# tact-switches.net
KiCad netlist of a schematic drawn in EAGLE
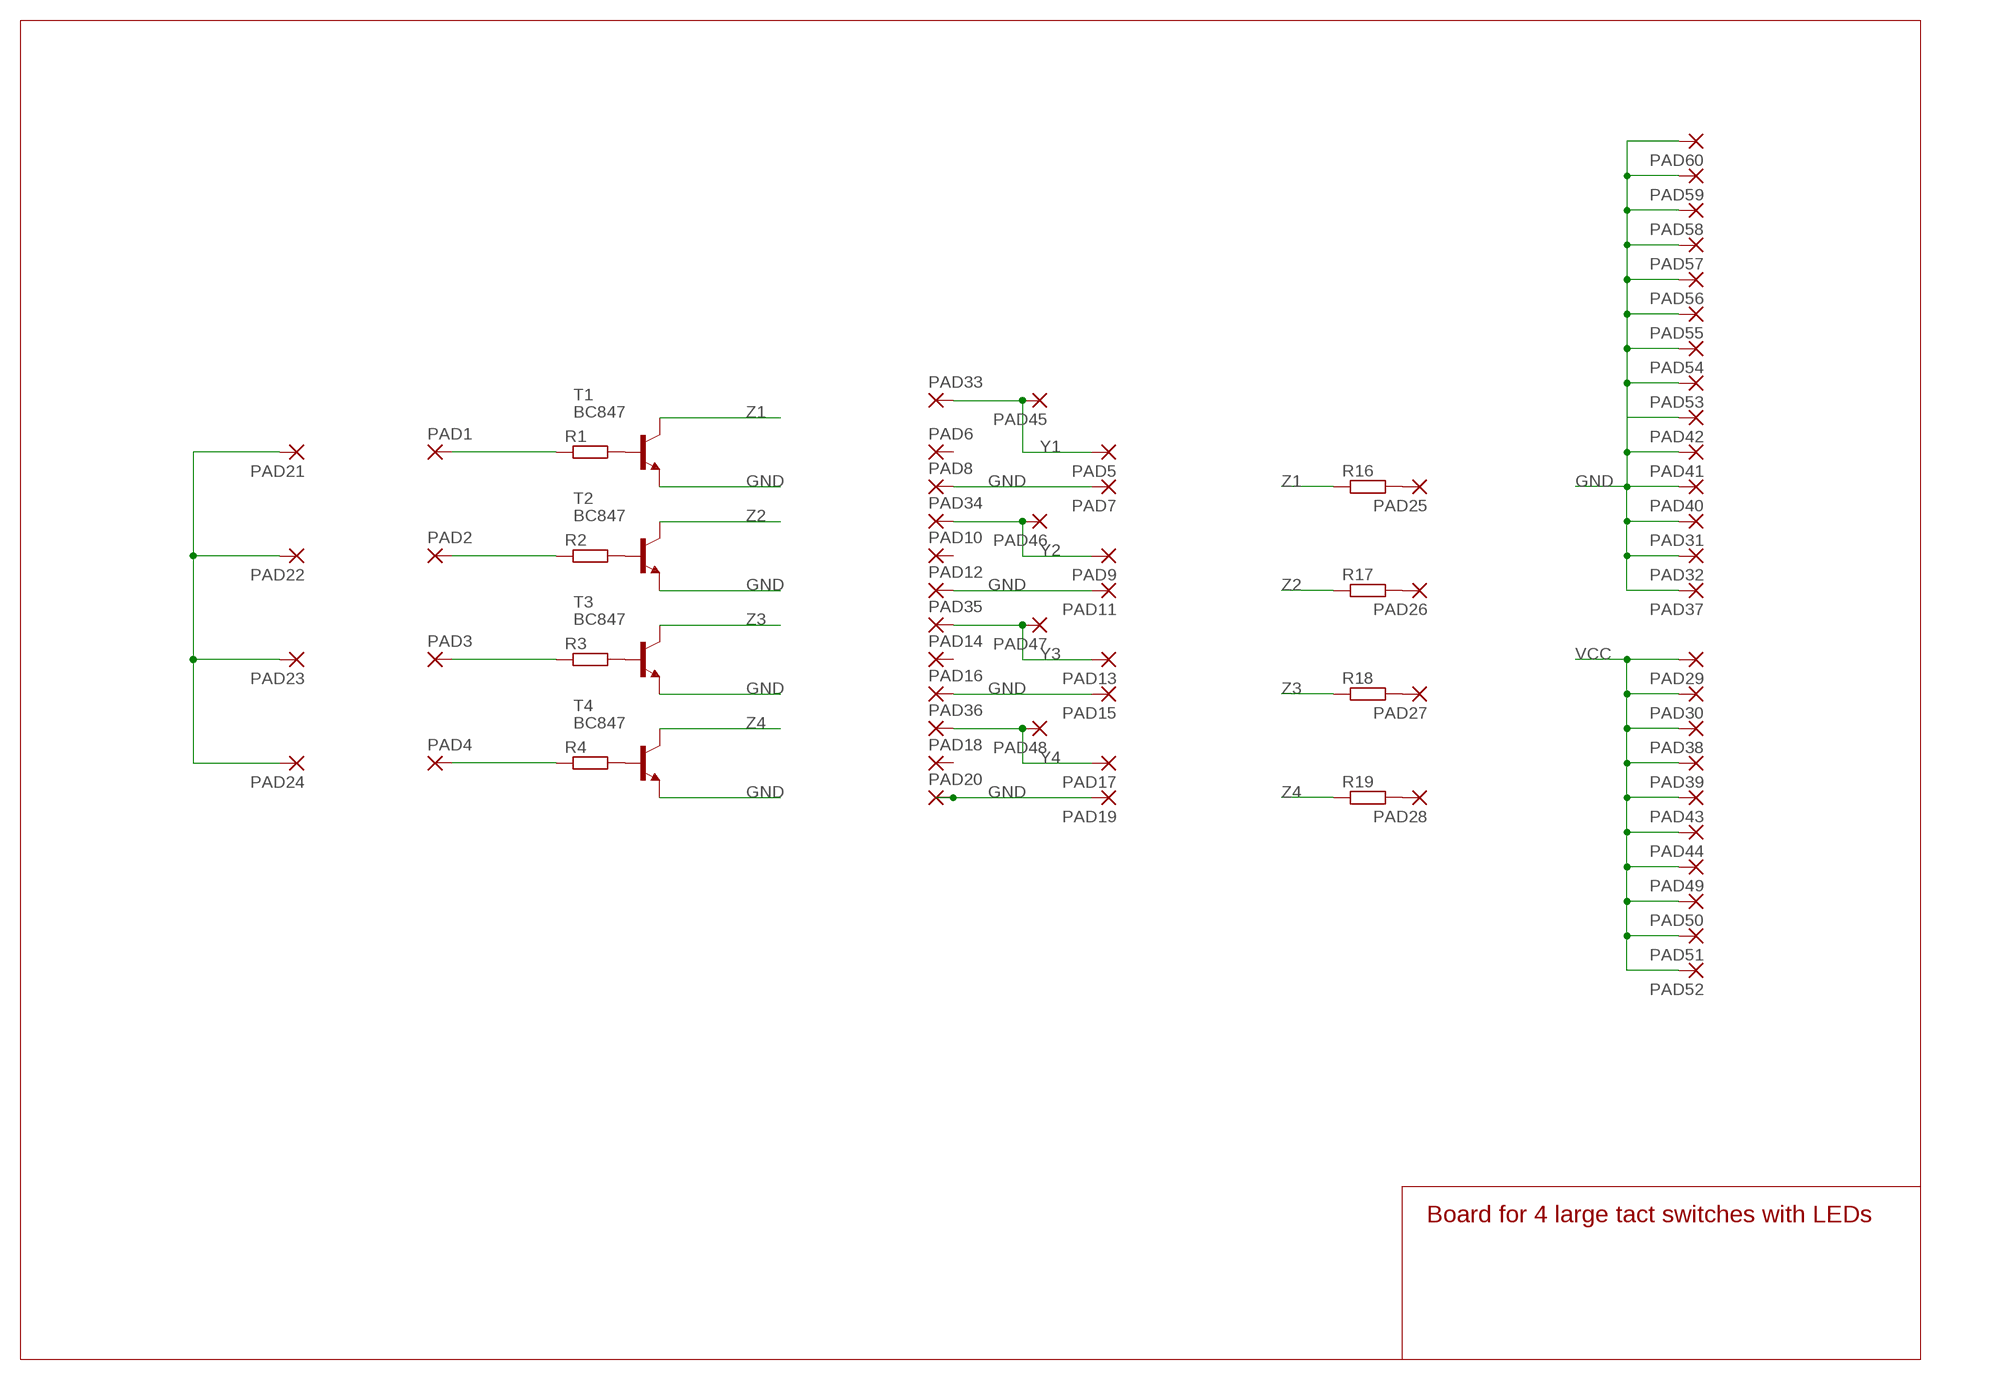
[diagram p0: schematic, sheet 1]

(export (version "E")
  (design (tool "Eeschema 10.0.6"))
  (components
    (comp (ref "PAD1")
      (value "1,6/0,8")
      (footprint "eagle-import:1,6_0,8")
      (libsource (lib "eagle-import") (part "1,6/0,8"))
    )
    (comp (ref "PAD2")
      (value "1,6/0,8")
      (footprint "eagle-import:1,6_0,8")
      (libsource (lib "eagle-import") (part "1,6/0,8"))
    )
    (comp (ref "PAD3")
      (value "1,6/0,8")
      (footprint "eagle-import:1,6_0,8")
      (libsource (lib "eagle-import") (part "1,6/0,8"))
    )
    (comp (ref "PAD4")
      (value "1,6/0,8")
      (footprint "eagle-import:1,6_0,8")
      (libsource (lib "eagle-import") (part "1,6/0,8"))
    )
    (comp (ref "PAD5")
      (value "1,6/0,8")
      (footprint "eagle-import:1,6_0,8")
      (libsource (lib "eagle-import") (part "1,6/0,8"))
    )
    (comp (ref "PAD6")
      (value "1,6/0,8")
      (footprint "eagle-import:1,6_0,8")
      (libsource (lib "eagle-import") (part "1,6/0,8"))
    )
    (comp (ref "PAD7")
      (value "1,6/0,8")
      (footprint "eagle-import:1,6_0,8")
      (libsource (lib "eagle-import") (part "1,6/0,8"))
    )
    (comp (ref "PAD8")
      (value "1,6/0,8")
      (footprint "eagle-import:1,6_0,8")
      (libsource (lib "eagle-import") (part "1,6/0,8"))
    )
    (comp (ref "PAD9")
      (value "1,6/0,8")
      (footprint "eagle-import:1,6_0,8")
      (libsource (lib "eagle-import") (part "1,6/0,8"))
    )
    (comp (ref "PAD10")
      (value "1,6/0,8")
      (footprint "eagle-import:1,6_0,8")
      (libsource (lib "eagle-import") (part "1,6/0,8"))
    )
    (comp (ref "PAD11")
      (value "1,6/0,8")
      (footprint "eagle-import:1,6_0,8")
      (libsource (lib "eagle-import") (part "1,6/0,8"))
    )
    (comp (ref "PAD12")
      (value "1,6/0,8")
      (footprint "eagle-import:1,6_0,8")
      (libsource (lib "eagle-import") (part "1,6/0,8"))
    )
    (comp (ref "PAD13")
      (value "1,6/0,8")
      (footprint "eagle-import:1,6_0,8")
      (libsource (lib "eagle-import") (part "1,6/0,8"))
    )
    (comp (ref "PAD14")
      (value "1,6/0,8")
      (footprint "eagle-import:1,6_0,8")
      (libsource (lib "eagle-import") (part "1,6/0,8"))
    )
    (comp (ref "PAD15")
      (value "1,6/0,8")
      (footprint "eagle-import:1,6_0,8")
      (libsource (lib "eagle-import") (part "1,6/0,8"))
    )
    (comp (ref "PAD16")
      (value "1,6/0,8")
      (footprint "eagle-import:1,6_0,8")
      (libsource (lib "eagle-import") (part "1,6/0,8"))
    )
    (comp (ref "PAD17")
      (value "1,6/0,8")
      (footprint "eagle-import:1,6_0,8")
      (libsource (lib "eagle-import") (part "1,6/0,8"))
    )
    (comp (ref "PAD18")
      (value "1,6/0,8")
      (footprint "eagle-import:1,6_0,8")
      (libsource (lib "eagle-import") (part "1,6/0,8"))
    )
    (comp (ref "PAD19")
      (value "1,6/0,8")
      (footprint "eagle-import:1,6_0,8")
      (libsource (lib "eagle-import") (part "1,6/0,8"))
    )
    (comp (ref "PAD20")
      (value "1,6/0,8")
      (footprint "eagle-import:1,6_0,8")
      (libsource (lib "eagle-import") (part "1,6/0,8"))
    )
    (comp (ref "PAD21")
      (value "1,6/0,8")
      (footprint "eagle-import:1,6_0,8")
      (libsource (lib "eagle-import") (part "1,6/0,8"))
    )
    (comp (ref "PAD22")
      (value "1,6/0,8")
      (footprint "eagle-import:1,6_0,8")
      (libsource (lib "eagle-import") (part "1,6/0,8"))
    )
    (comp (ref "PAD23")
      (value "1,6/0,8")
      (footprint "eagle-import:1,6_0,8")
      (libsource (lib "eagle-import") (part "1,6/0,8"))
    )
    (comp (ref "PAD24")
      (value "1,6/0,8")
      (footprint "eagle-import:1,6_0,8")
      (libsource (lib "eagle-import") (part "1,6/0,8"))
    )
    (comp (ref "PAD25")
      (value "1,6/0,8")
      (footprint "eagle-import:1,6_0,8")
      (libsource (lib "eagle-import") (part "1,6/0,8"))
    )
    (comp (ref "PAD26")
      (value "1,6/0,8")
      (footprint "eagle-import:1,6_0,8")
      (libsource (lib "eagle-import") (part "1,6/0,8"))
    )
    (comp (ref "PAD27")
      (value "1,6/0,8")
      (footprint "eagle-import:1,6_0,8")
      (libsource (lib "eagle-import") (part "1,6/0,8"))
    )
    (comp (ref "PAD28")
      (value "1,6/0,8")
      (footprint "eagle-import:1,6_0,8")
      (libsource (lib "eagle-import") (part "1,6/0,8"))
    )
    (comp (ref "PAD29")
      (value "1,6/0,8")
      (footprint "eagle-import:1,6_0,8")
      (libsource (lib "eagle-import") (part "1,6/0,8"))
    )
    (comp (ref "PAD30")
      (value "1,6/0,8")
      (footprint "eagle-import:1,6_0,8")
      (libsource (lib "eagle-import") (part "1,6/0,8"))
    )
    (comp (ref "PAD31")
      (value "1,6/0,8")
      (footprint "eagle-import:1,6_0,8")
      (libsource (lib "eagle-import") (part "1,6/0,8"))
    )
    (comp (ref "PAD32")
      (value "1,6/0,8")
      (footprint "eagle-import:1,6_0,8")
      (libsource (lib "eagle-import") (part "1,6/0,8"))
    )
    (comp (ref "PAD33")
      (value "1,6/0,8")
      (footprint "eagle-import:1,6_0,8")
      (libsource (lib "eagle-import") (part "1,6/0,8"))
    )
    (comp (ref "PAD34")
      (value "1,6/0,8")
      (footprint "eagle-import:1,6_0,8")
      (libsource (lib "eagle-import") (part "1,6/0,8"))
    )
    (comp (ref "PAD35")
      (value "1,6/0,8")
      (footprint "eagle-import:1,6_0,8")
      (libsource (lib "eagle-import") (part "1,6/0,8"))
    )
    (comp (ref "PAD36")
      (value "1,6/0,8")
      (footprint "eagle-import:1,6_0,8")
      (libsource (lib "eagle-import") (part "1,6/0,8"))
    )
    (comp (ref "PAD37")
      (value "1,6/0,8")
      (footprint "eagle-import:1,6_0,8")
      (libsource (lib "eagle-import") (part "1,6/0,8"))
    )
    (comp (ref "PAD38")
      (value "1,6/0,8")
      (footprint "eagle-import:1,6_0,8")
      (libsource (lib "eagle-import") (part "1,6/0,8"))
    )
    (comp (ref "PAD39")
      (value "1,6/0,8")
      (footprint "eagle-import:1,6_0,8")
      (libsource (lib "eagle-import") (part "1,6/0,8"))
    )
    (comp (ref "PAD40")
      (value "1,6/0,8")
      (footprint "eagle-import:1,6_0,8")
      (libsource (lib "eagle-import") (part "1,6/0,8"))
    )
    (comp (ref "PAD41")
      (value "1,6/0,8")
      (footprint "eagle-import:1,6_0,8")
      (libsource (lib "eagle-import") (part "1,6/0,8"))
    )
    (comp (ref "PAD42")
      (value "1,6/0,8")
      (footprint "eagle-import:1,6_0,8")
      (libsource (lib "eagle-import") (part "1,6/0,8"))
    )
    (comp (ref "PAD43")
      (value "1,6/0,8")
      (footprint "eagle-import:1,6_0,8")
      (libsource (lib "eagle-import") (part "1,6/0,8"))
    )
    (comp (ref "PAD44")
      (value "1,6/0,8")
      (footprint "eagle-import:1,6_0,8")
      (libsource (lib "eagle-import") (part "1,6/0,8"))
    )
    (comp (ref "PAD45")
      (value "1,6/0,8")
      (footprint "eagle-import:1,6_0,8")
      (libsource (lib "eagle-import") (part "1,6/0,8"))
    )
    (comp (ref "PAD46")
      (value "1,6/0,8")
      (footprint "eagle-import:1,6_0,8")
      (libsource (lib "eagle-import") (part "1,6/0,8"))
    )
    (comp (ref "PAD47")
      (value "1,6/0,8")
      (footprint "eagle-import:1,6_0,8")
      (libsource (lib "eagle-import") (part "1,6/0,8"))
    )
    (comp (ref "PAD48")
      (value "1,6/0,8")
      (footprint "eagle-import:1,6_0,8")
      (libsource (lib "eagle-import") (part "1,6/0,8"))
    )
    (comp (ref "PAD49")
      (value "1,6/0,8")
      (footprint "eagle-import:1,6_0,8")
      (libsource (lib "eagle-import") (part "1,6/0,8"))
    )
    (comp (ref "PAD50")
      (value "1,6/0,8")
      (footprint "eagle-import:1,6_0,8")
      (libsource (lib "eagle-import") (part "1,6/0,8"))
    )
    (comp (ref "PAD51")
      (value "1,6/0,8")
      (footprint "eagle-import:1,6_0,8")
      (libsource (lib "eagle-import") (part "1,6/0,8"))
    )
    (comp (ref "PAD52")
      (value "1,6/0,8")
      (footprint "eagle-import:1,6_0,8")
      (libsource (lib "eagle-import") (part "1,6/0,8"))
    )
    (comp (ref "PAD53")
      (value "1,6/0,8")
      (footprint "eagle-import:1,6_0,8")
      (libsource (lib "eagle-import") (part "1,6/0,8"))
    )
    (comp (ref "PAD54")
      (value "1,6/0,8")
      (footprint "eagle-import:1,6_0,8")
      (libsource (lib "eagle-import") (part "1,6/0,8"))
    )
    (comp (ref "PAD55")
      (value "1,6/0,8")
      (footprint "eagle-import:1,6_0,8")
      (libsource (lib "eagle-import") (part "1,6/0,8"))
    )
    (comp (ref "PAD56")
      (value "1,6/0,8")
      (footprint "eagle-import:1,6_0,8")
      (libsource (lib "eagle-import") (part "1,6/0,8"))
    )
    (comp (ref "PAD57")
      (value "1,6/0,8")
      (footprint "eagle-import:1,6_0,8")
      (libsource (lib "eagle-import") (part "1,6/0,8"))
    )
    (comp (ref "PAD58")
      (value "1,6/0,8")
      (footprint "eagle-import:1,6_0,8")
      (libsource (lib "eagle-import") (part "1,6/0,8"))
    )
    (comp (ref "PAD59")
      (value "1,6/0,8")
      (footprint "eagle-import:1,6_0,8")
      (libsource (lib "eagle-import") (part "1,6/0,8"))
    )
    (comp (ref "PAD60")
      (value "1,6/0,8")
      (footprint "eagle-import:1,6_0,8")
      (libsource (lib "eagle-import") (part "1,6/0,8"))
    )
    (comp (ref "R1")
      (value "R-EU_M0805")
      (footprint "eagle-import:M0805")
      (libsource (lib "eagle-import") (part "R-EU_M0805"))
    )
    (comp (ref "R2")
      (value "R-EU_M0805")
      (footprint "eagle-import:M0805")
      (libsource (lib "eagle-import") (part "R-EU_M0805"))
    )
    (comp (ref "R3")
      (value "R-EU_M0805")
      (footprint "eagle-import:M0805")
      (libsource (lib "eagle-import") (part "R-EU_M0805"))
    )
    (comp (ref "R4")
      (value "R-EU_M0805")
      (footprint "eagle-import:M0805")
      (libsource (lib "eagle-import") (part "R-EU_M0805"))
    )
    (comp (ref "R16")
      (value "R-EU_M0805")
      (footprint "eagle-import:M0805")
      (libsource (lib "eagle-import") (part "R-EU_M0805"))
    )
    (comp (ref "R17")
      (value "R-EU_M0805")
      (footprint "eagle-import:M0805")
      (libsource (lib "eagle-import") (part "R-EU_M0805"))
    )
    (comp (ref "R18")
      (value "R-EU_M0805")
      (footprint "eagle-import:M0805")
      (libsource (lib "eagle-import") (part "R-EU_M0805"))
    )
    (comp (ref "R19")
      (value "R-EU_M0805")
      (footprint "eagle-import:M0805")
      (libsource (lib "eagle-import") (part "R-EU_M0805"))
    )
    (comp (ref "T1")
      (value "BC847")
      (footprint "eagle-import:SOT23")
      (libsource (lib "eagle-import") (part "BC847"))
    )
    (comp (ref "T2")
      (value "BC847")
      (footprint "eagle-import:SOT23")
      (libsource (lib "eagle-import") (part "BC847"))
    )
    (comp (ref "T3")
      (value "BC847")
      (footprint "eagle-import:SOT23")
      (libsource (lib "eagle-import") (part "BC847"))
    )
    (comp (ref "T4")
      (value "BC847")
      (footprint "eagle-import:SOT23")
      (libsource (lib "eagle-import") (part "BC847"))
    )
  )
  (nets
    (net (code "1") (name "/GND") (class "Default")
      (node (ref "PAD11") (pin "1") (pinfunction "P_1") (pintype "passive"))
      (node (ref "PAD12") (pin "1") (pinfunction "P_1") (pintype "passive"))
      (node (ref "PAD15") (pin "1") (pinfunction "P_1") (pintype "passive"))
      (node (ref "PAD16") (pin "1") (pinfunction "P_1") (pintype "passive"))
      (node (ref "PAD19") (pin "1") (pinfunction "P_1") (pintype "passive"))
      (node (ref "PAD20") (pin "1") (pinfunction "P_1") (pintype "passive"))
      (node (ref "PAD31") (pin "1") (pinfunction "P_1") (pintype "passive"))
      (node (ref "PAD32") (pin "1") (pinfunction "P_1") (pintype "passive"))
      (node (ref "PAD37") (pin "1") (pinfunction "P_1") (pintype "passive"))
      (node (ref "PAD40") (pin "1") (pinfunction "P_1") (pintype "passive"))
      (node (ref "PAD41") (pin "1") (pinfunction "P_1") (pintype "passive"))
      (node (ref "PAD42") (pin "1") (pinfunction "P_1") (pintype "passive"))
      (node (ref "PAD53") (pin "1") (pinfunction "P_1") (pintype "passive"))
      (node (ref "PAD54") (pin "1") (pinfunction "P_1") (pintype "passive"))
      (node (ref "PAD55") (pin "1") (pinfunction "P_1") (pintype "passive"))
      (node (ref "PAD56") (pin "1") (pinfunction "P_1") (pintype "passive"))
      (node (ref "PAD57") (pin "1") (pinfunction "P_1") (pintype "passive"))
      (node (ref "PAD58") (pin "1") (pinfunction "P_1") (pintype "passive"))
      (node (ref "PAD59") (pin "1") (pinfunction "P_1") (pintype "passive"))
      (node (ref "PAD60") (pin "1") (pinfunction "P_1") (pintype "passive"))
      (node (ref "PAD7") (pin "1") (pinfunction "P_1") (pintype "passive"))
      (node (ref "PAD8") (pin "1") (pinfunction "P_1") (pintype "passive"))
      (node (ref "T1") (pin "2") (pinfunction "E_2") (pintype "passive"))
      (node (ref "T2") (pin "2") (pinfunction "E_2") (pintype "passive"))
      (node (ref "T3") (pin "2") (pinfunction "E_2") (pintype "passive"))
      (node (ref "T4") (pin "2") (pinfunction "E_2") (pintype "passive"))
    )
    (net (code "2") (name "/VCC") (class "Default")
      (node (ref "PAD29") (pin "1") (pinfunction "P_1") (pintype "passive"))
      (node (ref "PAD30") (pin "1") (pinfunction "P_1") (pintype "passive"))
      (node (ref "PAD38") (pin "1") (pinfunction "P_1") (pintype "passive"))
      (node (ref "PAD39") (pin "1") (pinfunction "P_1") (pintype "passive"))
      (node (ref "PAD43") (pin "1") (pinfunction "P_1") (pintype "passive"))
      (node (ref "PAD44") (pin "1") (pinfunction "P_1") (pintype "passive"))
      (node (ref "PAD49") (pin "1") (pinfunction "P_1") (pintype "passive"))
      (node (ref "PAD50") (pin "1") (pinfunction "P_1") (pintype "passive"))
      (node (ref "PAD51") (pin "1") (pinfunction "P_1") (pintype "passive"))
      (node (ref "PAD52") (pin "1") (pinfunction "P_1") (pintype "passive"))
    )
    (net (code "3") (name "/Y1") (class "Default")
      (node (ref "PAD33") (pin "1") (pinfunction "P_1") (pintype "passive"))
      (node (ref "PAD45") (pin "1") (pinfunction "P_1") (pintype "passive"))
      (node (ref "PAD5") (pin "1") (pinfunction "P_1") (pintype "passive"))
    )
    (net (code "4") (name "/Y2") (class "Default")
      (node (ref "PAD34") (pin "1") (pinfunction "P_1") (pintype "passive"))
      (node (ref "PAD46") (pin "1") (pinfunction "P_1") (pintype "passive"))
      (node (ref "PAD9") (pin "1") (pinfunction "P_1") (pintype "passive"))
    )
    (net (code "5") (name "/Y3") (class "Default")
      (node (ref "PAD13") (pin "1") (pinfunction "P_1") (pintype "passive"))
      (node (ref "PAD35") (pin "1") (pinfunction "P_1") (pintype "passive"))
      (node (ref "PAD47") (pin "1") (pinfunction "P_1") (pintype "passive"))
    )
    (net (code "6") (name "/Y4") (class "Default")
      (node (ref "PAD17") (pin "1") (pinfunction "P_1") (pintype "passive"))
      (node (ref "PAD36") (pin "1") (pinfunction "P_1") (pintype "passive"))
      (node (ref "PAD48") (pin "1") (pinfunction "P_1") (pintype "passive"))
    )
    (net (code "7") (name "/Z1") (class "Default")
      (node (ref "R16") (pin "1") (pinfunction "1_1") (pintype "passive"))
      (node (ref "T1") (pin "3") (pinfunction "C_3") (pintype "passive"))
    )
    (net (code "8") (name "/Z2") (class "Default")
      (node (ref "R17") (pin "1") (pinfunction "1_1") (pintype "passive"))
      (node (ref "T2") (pin "3") (pinfunction "C_3") (pintype "passive"))
    )
    (net (code "9") (name "/Z3") (class "Default")
      (node (ref "R18") (pin "1") (pinfunction "1_1") (pintype "passive"))
      (node (ref "T3") (pin "3") (pinfunction "C_3") (pintype "passive"))
    )
    (net (code "10") (name "/Z4") (class "Default")
      (node (ref "R19") (pin "1") (pinfunction "1_1") (pintype "passive"))
      (node (ref "T4") (pin "3") (pinfunction "C_3") (pintype "passive"))
    )
    (net (code "11") (name "Net-(PAD1-P)") (class "Default")
      (node (ref "PAD1") (pin "1") (pinfunction "P_1") (pintype "passive"))
      (node (ref "R1") (pin "1") (pinfunction "1_1") (pintype "passive"))
    )
    (net (code "12") (name "Net-(PAD2-P)") (class "Default")
      (node (ref "PAD2") (pin "1") (pinfunction "P_1") (pintype "passive"))
      (node (ref "R2") (pin "1") (pinfunction "1_1") (pintype "passive"))
    )
    (net (code "13") (name "Net-(PAD3-P)") (class "Default")
      (node (ref "PAD3") (pin "1") (pinfunction "P_1") (pintype "passive"))
      (node (ref "R3") (pin "1") (pinfunction "1_1") (pintype "passive"))
    )
    (net (code "14") (name "Net-(PAD4-P)") (class "Default")
      (node (ref "PAD4") (pin "1") (pinfunction "P_1") (pintype "passive"))
      (node (ref "R4") (pin "1") (pinfunction "1_1") (pintype "passive"))
    )
    (net (code "15") (name "Net-(PAD21-P)") (class "Default")
      (node (ref "PAD21") (pin "1") (pinfunction "P_1") (pintype "passive"))
      (node (ref "PAD22") (pin "1") (pinfunction "P_1") (pintype "passive"))
      (node (ref "PAD23") (pin "1") (pinfunction "P_1") (pintype "passive"))
      (node (ref "PAD24") (pin "1") (pinfunction "P_1") (pintype "passive"))
    )
    (net (code "16") (name "Net-(PAD25-P)") (class "Default")
      (node (ref "PAD25") (pin "1") (pinfunction "P_1") (pintype "passive"))
      (node (ref "R16") (pin "2") (pinfunction "2_2") (pintype "passive"))
    )
    (net (code "17") (name "Net-(PAD26-P)") (class "Default")
      (node (ref "PAD26") (pin "1") (pinfunction "P_1") (pintype "passive"))
      (node (ref "R17") (pin "2") (pinfunction "2_2") (pintype "passive"))
    )
    (net (code "18") (name "Net-(PAD27-P)") (class "Default")
      (node (ref "PAD27") (pin "1") (pinfunction "P_1") (pintype "passive"))
      (node (ref "R18") (pin "2") (pinfunction "2_2") (pintype "passive"))
    )
    (net (code "19") (name "Net-(PAD28-P)") (class "Default")
      (node (ref "PAD28") (pin "1") (pinfunction "P_1") (pintype "passive"))
      (node (ref "R19") (pin "2") (pinfunction "2_2") (pintype "passive"))
    )
    (net (code "20") (name "Net-(T1-B)") (class "Default")
      (node (ref "R1") (pin "2") (pinfunction "2_2") (pintype "passive"))
      (node (ref "T1") (pin "1") (pinfunction "B_1") (pintype "passive"))
    )
    (net (code "21") (name "Net-(T2-B)") (class "Default")
      (node (ref "R2") (pin "2") (pinfunction "2_2") (pintype "passive"))
      (node (ref "T2") (pin "1") (pinfunction "B_1") (pintype "passive"))
    )
    (net (code "22") (name "Net-(T3-B)") (class "Default")
      (node (ref "R3") (pin "2") (pinfunction "2_2") (pintype "passive"))
      (node (ref "T3") (pin "1") (pinfunction "B_1") (pintype "passive"))
    )
    (net (code "23") (name "Net-(T4-B)") (class "Default")
      (node (ref "R4") (pin "2") (pinfunction "2_2") (pintype "passive"))
      (node (ref "T4") (pin "1") (pinfunction "B_1") (pintype "passive"))
    )
    (net (code "24") (name "unconnected-(PAD6-P-Pad1)") (class "Default")
      (node (ref "PAD6") (pin "1") (pinfunction "P_1") (pintype "passive"))
    )
    (net (code "25") (name "unconnected-(PAD10-P-Pad1)") (class "Default")
      (node (ref "PAD10") (pin "1") (pinfunction "P_1") (pintype "passive"))
    )
    (net (code "26") (name "unconnected-(PAD14-P-Pad1)") (class "Default")
      (node (ref "PAD14") (pin "1") (pinfunction "P_1") (pintype "passive"))
    )
    (net (code "27") (name "unconnected-(PAD18-P-Pad1)") (class "Default")
      (node (ref "PAD18") (pin "1") (pinfunction "P_1") (pintype "passive"))
    )
  )
)
